# schematic.net
KiCad netlist of a schematic drawn in EAGLE
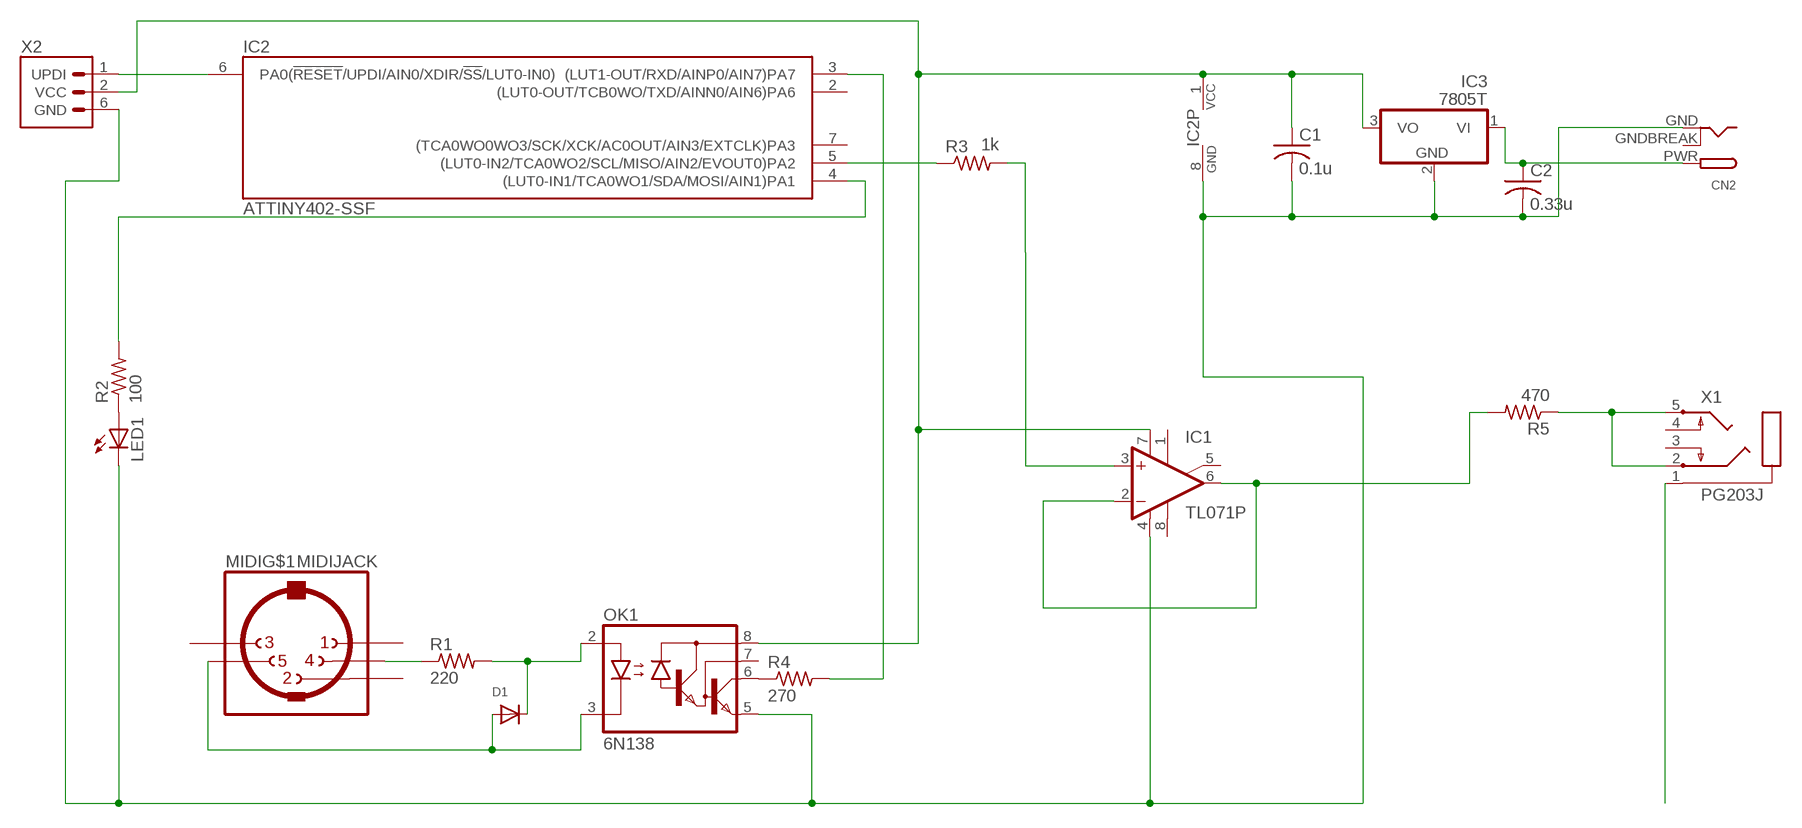
[diagram p0: schematic, sheet 1]

(export (version "E")
  (design (tool "Eeschema 10.0.6"))
  (components
    (comp (ref "C1")
      (value "0.1u")
      (footprint "eagle-import:C075-032X103")
      (libsource (lib "eagle-import") (part "C-US075-032X103"))
    )
    (comp (ref "C2")
      (value "0.33u")
      (footprint "eagle-import:C075-032X103")
      (libsource (lib "eagle-import") (part "C-US075-032X103"))
    )
    (comp (ref "CN2")
      (value "DCBARRELPTH")
      (footprint "eagle-import:DCJACK_2MM_PTH")
      (libsource (lib "eagle-import") (part "DCBARRELPTH"))
    )
    (comp (ref "D1")
      (value "DIODEDO-1N4148")
      (footprint "eagle-import:DO-1N4148")
      (libsource (lib "eagle-import") (part "DIODEDO-1N4148"))
    )
    (comp (ref "IC1")
      (value "TL071P")
      (footprint "eagle-import:DIL08")
      (libsource (lib "eagle-import") (part "TL071P"))
    )
    (comp (ref "IC2")
      (value "ATTINY402-SSF")
      (footprint "eagle-import:SO8")
      (libsource (lib "eagle-import") (part "ATTINY02-SSF4"))
    )
    (comp (ref "IC3")
      (value "7805T")
      (footprint "eagle-import:TO220H")
      (libsource (lib "eagle-import") (part "78T05"))
    )
    (comp (ref "LED1")
      (value "LEDSFH480")
      (footprint "eagle-import:SFH480")
      (libsource (lib "eagle-import") (part "LEDSFH480"))
    )
    (comp (ref "MIDI")
      (value "MIDIJACK")
      (footprint "eagle-import:CP-2350")
      (libsource (lib "eagle-import") (part "MIDIJACK"))
    )
    (comp (ref "OK1")
      (value "6N138")
      (footprint "eagle-import:DIL08")
      (fields (field (name "MF") "VISHAY/TELEFUNKEN"))
      (libsource (lib "eagle-import") (part "6N138"))
    )
    (comp (ref "R1")
      (value "220")
      (footprint "eagle-import:0207_10")
      (libsource (lib "eagle-import") (part "R-US_0207/10"))
    )
    (comp (ref "R2")
      (value "100")
      (footprint "eagle-import:0207_10")
      (libsource (lib "eagle-import") (part "R-US_0207/10"))
    )
    (comp (ref "R3")
      (value "1k")
      (footprint "eagle-import:0207_10")
      (libsource (lib "eagle-import") (part "R-US_0207/10"))
    )
    (comp (ref "R4")
      (value "270")
      (footprint "eagle-import:0207_10")
      (libsource (lib "eagle-import") (part "R-US_0207/10"))
    )
    (comp (ref "R5")
      (value "470")
      (footprint "eagle-import:0207_10")
      (libsource (lib "eagle-import") (part "R-US_0207/10"))
    )
    (comp (ref "X1")
      (value "PG203J")
      (footprint "eagle-import:PG203J")
      (libsource (lib "eagle-import") (part "PG203J"))
    )
    (comp (ref "X2")
      (value "UPDITHT_100MIL")
      (footprint "eagle-import:PINHEADER_2R03_100MIL")
      (libsource (lib "eagle-import") (part "UPDITHT_100MIL"))
    )
  )
  (nets
    (net (code "1") (name "/GNDBREAK") (class "Default")
      (node (ref "CN2") (pin "GNDBREAK") (pinfunction "GNDBREAK_GNDBREAK") (pintype "power_in"))
    )
    (net (code "2") (name "Net-(IC1-+IN)") (class "Default")
      (node (ref "IC1") (pin "3") (pinfunction "+IN_3") (pintype "input"))
      (node (ref "R3") (pin "2") (pinfunction "2_2") (pintype "passive"))
    )
    (net (code "3") (name "Net-(IC1--IN)") (class "Default")
      (node (ref "IC1") (pin "2") (pinfunction "-IN_2") (pintype "input"))
      (node (ref "IC1") (pin "6") (pinfunction "OUT_6") (pintype "output"))
      (node (ref "R5") (pin "2") (pinfunction "2_2") (pintype "passive"))
    )
    (net (code "4") (name "Net-(IC1-V+)") (class "Default")
      (node (ref "C1") (pin "1") (pinfunction "1_1") (pintype "passive"))
      (node (ref "IC1") (pin "7") (pinfunction "V+_7") (pintype "power_in"))
      (node (ref "IC2") (pin "1") (pinfunction "VCC_1") (pintype "power_in"))
      (node (ref "IC3") (pin "3") (pinfunction "VO_3") (pintype "passive"))
      (node (ref "OK1") (pin "8") (pinfunction "VCC_8") (pintype "passive"))
      (node (ref "X2") (pin "2") (pinfunction "VCC_2") (pintype "power_in"))
    )
    (net (code "5") (name "Net-(IC1-V-)") (class "Default")
      (node (ref "C1") (pin "2") (pinfunction "2_2") (pintype "passive"))
      (node (ref "C2") (pin "2") (pinfunction "2_2") (pintype "passive"))
      (node (ref "CN2") (pin "GND") (pinfunction "GND_GND") (pintype "power_in"))
      (node (ref "IC1") (pin "4") (pinfunction "V-_4") (pintype "power_in"))
      (node (ref "IC2") (pin "8") (pinfunction "GND_8") (pintype "power_in"))
      (node (ref "IC3") (pin "2") (pinfunction "GND_2") (pintype "passive"))
      (node (ref "LED1") (pin "K") (pinfunction "C_K") (pintype "passive"))
      (node (ref "OK1") (pin "5") (pinfunction "GND_5") (pintype "passive"))
      (node (ref "X2") (pin "6") (pinfunction "GND_6") (pintype "power_in"))
    )
    (net (code "6") (name "Net-(IC2A-(LUT0-IN1{slash}TCA0WO1{slash}SDA{slash}MOSI{slash}AIN1)PA1)") (class "Default")
      (node (ref "IC2") (pin "4") (pinfunction "(LUT0-IN1/TCA0WO1/SDA/MOSI/AIN1)PA1_4") (pintype "bidirectional"))
      (node (ref "R2") (pin "2") (pinfunction "2_2") (pintype "passive"))
    )
    (net (code "7") (name "Net-(IC2A-(LUT0-IN2{slash}TCA0WO2{slash}SCL{slash}MISO{slash}AIN2{slash}EVOUT0)PA2)") (class "Default")
      (node (ref "IC2") (pin "5") (pinfunction "(LUT0-IN2/TCA0WO2/SCL/MISO/AIN2/EVOUT0)PA2_5") (pintype "bidirectional"))
      (node (ref "R3") (pin "1") (pinfunction "1_1") (pintype "passive"))
    )
    (net (code "8") (name "Net-(IC2A-(LUT1-OUT{slash}RXD{slash}AINP0{slash}AIN7)PA7)") (class "Default")
      (node (ref "IC2") (pin "3") (pinfunction "(LUT1-OUT/RXD/AINP0/AIN7)PA7_3") (pintype "bidirectional"))
      (node (ref "R4") (pin "2") (pinfunction "2_2") (pintype "passive"))
    )
    (net (code "9") (name "Net-(IC2A-PA0(~{RESET}{slash}UPDI{slash}AIN0{slash}XDIR{slash}~{SS}{slash}LUT0-IN0))") (class "Default")
      (node (ref "IC2") (pin "6") (pinfunction "PA0(~{RESET}/UPDI/AIN0/XDIR/~{SS}/LUT0-IN0)_6") (pintype "bidirectional"))
      (node (ref "X2") (pin "1") (pinfunction "UPDI_1") (pintype "bidirectional"))
    )
    (net (code "10") (name "Net-(IC3-VI)") (class "Default")
      (node (ref "C2") (pin "1") (pinfunction "1_1") (pintype "passive"))
      (node (ref "CN2") (pin "PWR") (pinfunction "PWR_PWR") (pintype "power_in"))
      (node (ref "IC3") (pin "1") (pinfunction "VI_1") (pintype "input"))
    )
    (net (code "11") (name "Net-(LED1-PadA)") (class "Default")
      (node (ref "LED1") (pin "A") (pinfunction "A_A") (pintype "passive"))
      (node (ref "R2") (pin "1") (pinfunction "1_1") (pintype "passive"))
    )
    (net (code "12") (name "Net-(MIDI-Pad4)") (class "Default")
      (node (ref "MIDI") (pin "4") (pinfunction "4_4") (pintype "passive"))
      (node (ref "R1") (pin "1") (pinfunction "1_1") (pintype "passive"))
    )
    (net (code "13") (name "Net-(OK1-A)") (class "Default")
      (node (ref "D1") (pin "C") (pinfunction "C_C") (pintype "passive"))
      (node (ref "OK1") (pin "2") (pinfunction "A_2") (pintype "passive"))
      (node (ref "R1") (pin "2") (pinfunction "2_2") (pintype "passive"))
    )
    (net (code "14") (name "Net-(OK1-C)") (class "Default")
      (node (ref "D1") (pin "A") (pinfunction "A_A") (pintype "passive"))
      (node (ref "MIDI") (pin "5") (pinfunction "5_5") (pintype "passive"))
      (node (ref "OK1") (pin "3") (pinfunction "C_3") (pintype "passive"))
    )
    (net (code "15") (name "Net-(OK1-VO)") (class "Default")
      (node (ref "OK1") (pin "6") (pinfunction "VO_6") (pintype "passive"))
      (node (ref "R4") (pin "1") (pinfunction "1_1") (pintype "passive"))
    )
    (net (code "16") (name "Net-(R5-Pad1)") (class "Default")
      (node (ref "R5") (pin "1") (pinfunction "1_1") (pintype "passive"))
      (node (ref "X1") (pin "2") (pinfunction "2_2") (pintype "passive"))
      (node (ref "X1") (pin "5") (pinfunction "5_5") (pintype "passive"))
    )
    (net (code "17") (name "unconnected-(IC1-ON1-Pad1)") (class "Default")
      (node (ref "IC1") (pin "1") (pinfunction "ON1_1") (pintype "passive"))
    )
    (net (code "18") (name "unconnected-(IC1-ON2-Pad5)") (class "Default")
      (node (ref "IC1") (pin "5") (pinfunction "ON2_5") (pintype "passive"))
    )
    (net (code "19") (name "unconnected-(IC1-OPT-Pad8)") (class "Default")
      (node (ref "IC1") (pin "8") (pinfunction "OPT_8") (pintype "passive"))
    )
    (net (code "20") (name "unconnected-(IC2A-(LUT0-OUT{slash}TCB0WO{slash}TXD{slash}AINN0{slash}AIN6)PA6-Pad2)") (class "Default")
      (node (ref "IC2") (pin "2") (pinfunction "(LUT0-OUT/TCB0WO/TXD/AINN0/AIN6)PA6_2") (pintype "bidirectional"))
    )
    (net (code "21") (name "unconnected-(IC2A-(TCA0WO0WO3{slash}SCK{slash}XCK{slash}AC0OUT{slash}AIN3{slash}EXTCLK)PA3-Pad7)") (class "Default")
      (node (ref "IC2") (pin "7") (pinfunction "(TCA0WO0WO3/SCK/XCK/AC0OUT/AIN3/EXTCLK)PA3_7") (pintype "bidirectional"))
    )
    (net (code "22") (name "unconnected-(MIDI-Pad1)") (class "Default")
      (node (ref "MIDI") (pin "1") (pinfunction "1_1") (pintype "passive"))
    )
    (net (code "23") (name "unconnected-(MIDI-Pad2)") (class "Default")
      (node (ref "MIDI") (pin "2") (pinfunction "2_2") (pintype "passive"))
    )
    (net (code "24") (name "unconnected-(MIDI-Pad3)") (class "Default")
      (node (ref "MIDI") (pin "3") (pinfunction "3_3") (pintype "passive"))
    )
    (net (code "25") (name "unconnected-(OK1-VB-Pad7)") (class "Default")
      (node (ref "OK1") (pin "7") (pinfunction "VB_7") (pintype "passive"))
    )
    (net (code "26") (name "unconnected-(X1-Pad1)") (class "Default")
      (node (ref "X1") (pin "1") (pinfunction "1_1") (pintype "passive"))
    )
    (net (code "27") (name "unconnected-(X1-Pad3)") (class "Default")
      (node (ref "X1") (pin "3") (pinfunction "3_3") (pintype "passive"))
    )
    (net (code "28") (name "unconnected-(X1-Pad4)") (class "Default")
      (node (ref "X1") (pin "4") (pinfunction "4_4") (pintype "passive"))
    )
  )
)
